# led7Seg_2.net
KiCad netlist of a schematic drawn in Altium Designer
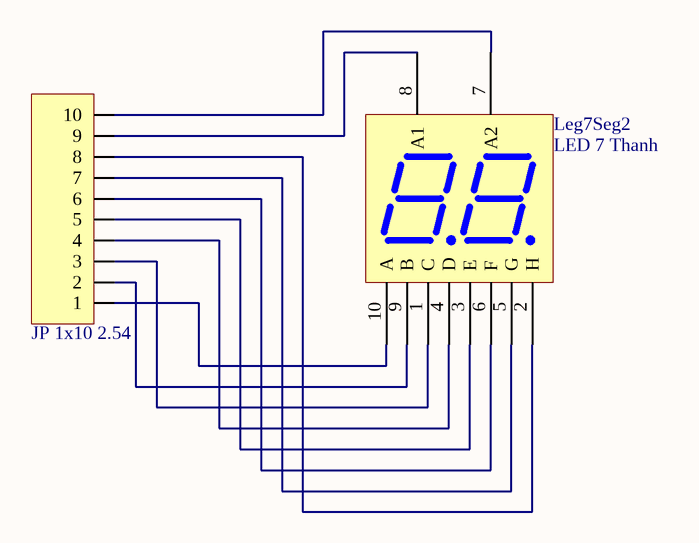
[diagram p0: led7Seg_2.SchDoc]

(export (version "E")
  (design (tool "Eeschema 10.0.6"))
  (components
    (comp (ref "JP10")
      (value "JP 1x10 2.54")
      (footprint "JP 1x10 DT")
      (description "Cắm")
      (libsource (lib "Altium_Lib_by_KhueNguyenCreator") (part "JP 1x10 2.54 Duc Thang"))
    )
    (comp (ref "Leg7Seg2")
      (value "LED 7 Thanh")
      (footprint "LED 7x2 0.56")
      (description "Dán")
      (libsource (lib "Altium_Lib_by_KhueNguyenCreator") (part "LED 7x2 0.56 Anot"))
    )
  )
  (nets
    (net (code "1") (name "Net-(Leg7Seg2-A)") (class "Default")
      (node (ref "JP10") (pin "1") (pinfunction "1_1") (pintype "passive"))
      (node (ref "Leg7Seg2") (pin "10") (pinfunction "A_10") (pintype "passive"))
    )
    (net (code "2") (name "Net-(Leg7Seg2-A1)") (class "Default")
      (node (ref "JP10") (pin "9") (pinfunction "9_9") (pintype "passive"))
      (node (ref "Leg7Seg2") (pin "8") (pinfunction "A1_8") (pintype "passive"))
    )
    (net (code "3") (name "Net-(Leg7Seg2-A2)") (class "Default")
      (node (ref "JP10") (pin "10") (pinfunction "10_10") (pintype "passive"))
      (node (ref "Leg7Seg2") (pin "7") (pinfunction "A2_7") (pintype "passive"))
    )
    (net (code "4") (name "Net-(Leg7Seg2-B)") (class "Default")
      (node (ref "JP10") (pin "2") (pinfunction "2_2") (pintype "passive"))
      (node (ref "Leg7Seg2") (pin "9") (pinfunction "B_9") (pintype "passive"))
    )
    (net (code "5") (name "Net-(Leg7Seg2-C)") (class "Default")
      (node (ref "JP10") (pin "3") (pinfunction "3_3") (pintype "passive"))
      (node (ref "Leg7Seg2") (pin "1") (pinfunction "C_1") (pintype "passive"))
    )
    (net (code "6") (name "Net-(Leg7Seg2-D)") (class "Default")
      (node (ref "JP10") (pin "4") (pinfunction "4_4") (pintype "passive"))
      (node (ref "Leg7Seg2") (pin "4") (pinfunction "D_4") (pintype "passive"))
    )
    (net (code "7") (name "Net-(Leg7Seg2-E)") (class "Default")
      (node (ref "JP10") (pin "5") (pinfunction "5_5") (pintype "passive"))
      (node (ref "Leg7Seg2") (pin "3") (pinfunction "E_3") (pintype "passive"))
    )
    (net (code "8") (name "Net-(Leg7Seg2-F)") (class "Default")
      (node (ref "JP10") (pin "6") (pinfunction "6_6") (pintype "passive"))
      (node (ref "Leg7Seg2") (pin "6") (pinfunction "F_6") (pintype "passive"))
    )
    (net (code "9") (name "Net-(Leg7Seg2-G)") (class "Default")
      (node (ref "JP10") (pin "7") (pinfunction "7_7") (pintype "passive"))
      (node (ref "Leg7Seg2") (pin "5") (pinfunction "G_5") (pintype "passive"))
    )
    (net (code "10") (name "Net-(Leg7Seg2-H)") (class "Default")
      (node (ref "JP10") (pin "8") (pinfunction "8_8") (pintype "passive"))
      (node (ref "Leg7Seg2") (pin "2") (pinfunction "H_2") (pintype "passive"))
    )
  )
)
